# ui_front.net
KiCad netlist of a schematic drawn in Altium Designer
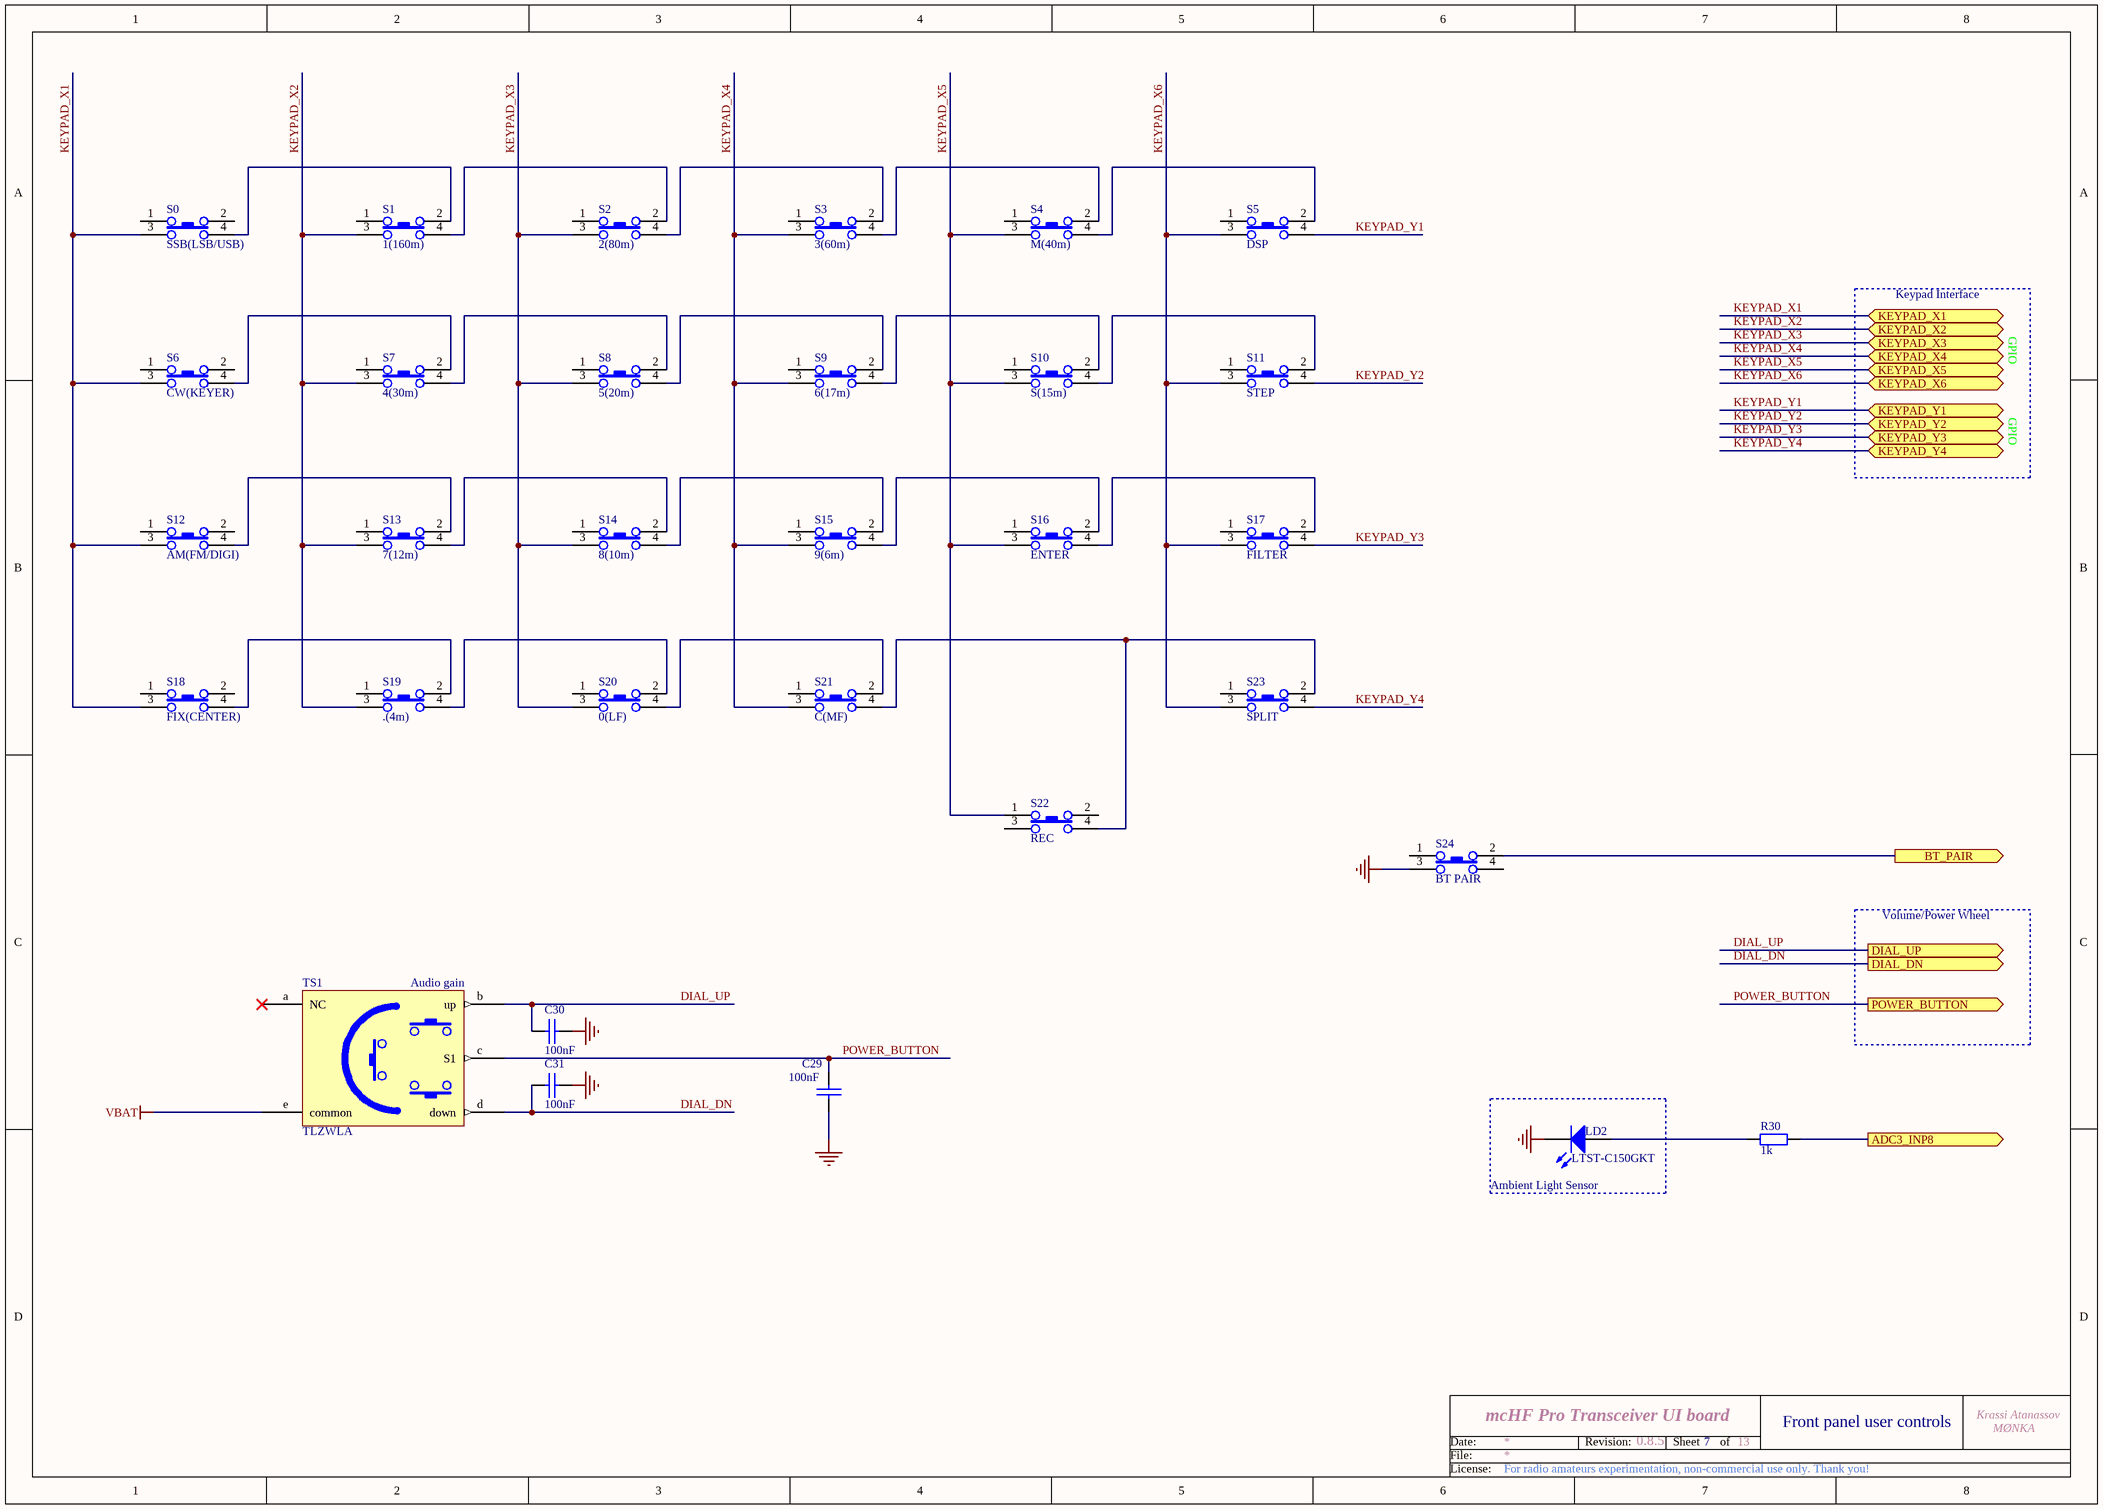
[diagram p0: ui_front.SchDoc]

(export (version "E")
  (design (tool "Eeschema 10.0.6"))
  (components
    (comp (ref "C29")
      (value "100nF")
      (footprint "0805")
      (description "Capacitor")
      (libsource (lib "mcHF_ui") (part "CAP"))
    )
    (comp (ref "C30")
      (value "100nF")
      (footprint "0805")
      (description "Capacitor")
      (libsource (lib "mcHF_ui") (part "CAP"))
    )
    (comp (ref "C31")
      (value "100nF")
      (footprint "0805")
      (description "Capacitor")
      (libsource (lib "mcHF_ui") (part "CAP"))
    )
    (comp (ref "LD2")
      (value "LTST-C150GKT")
      (footprint "1206_Elec_Cap")
      (description "LED 3mm")
      (libsource (lib "mcHF_ui") (part "LED2"))
    )
    (comp (ref "R30")
      (value "1k")
      (footprint "0805")
      (description "Resistor")
      (libsource (lib "mcHF_ui") (part "RES"))
    )
    (comp (ref "S0")
      (value "SSB(LSB/USB)")
      (footprint "BUTTON_SMD2")
      (description "Push Button")
      (libsource (lib "__ui") (part "SW-PB"))
    )
    (comp (ref "S1")
      (value "1(160m)")
      (footprint "BUTTON_SMD2")
      (description "Push Button")
      (libsource (lib "__ui") (part "SW-PB"))
    )
    (comp (ref "S2")
      (value "2(80m)")
      (footprint "BUTTON_SMD2")
      (description "Push Button")
      (libsource (lib "__ui") (part "SW-PB"))
    )
    (comp (ref "S3")
      (value "3(60m)")
      (footprint "BUTTON_SMD2")
      (description "Push Button")
      (libsource (lib "__ui") (part "SW-PB"))
    )
    (comp (ref "S4")
      (value "M(40m)")
      (footprint "BUTTON_SMD2")
      (description "Push Button")
      (libsource (lib "__ui") (part "SW-PB"))
    )
    (comp (ref "S5")
      (value "DSP")
      (footprint "BUTTON_SMD2")
      (description "Push Button")
      (libsource (lib "__ui") (part "SW-PB"))
    )
    (comp (ref "S6")
      (value "CW(KEYER)")
      (footprint "BUTTON_SMD2")
      (description "Push Button")
      (libsource (lib "__ui") (part "SW-PB"))
    )
    (comp (ref "S7")
      (value "4(30m)")
      (footprint "BUTTON_SMD2")
      (description "Push Button")
      (libsource (lib "__ui") (part "SW-PB"))
    )
    (comp (ref "S8")
      (value "5(20m)")
      (footprint "BUTTON_SMD2")
      (description "Push Button")
      (libsource (lib "__ui") (part "SW-PB"))
    )
    (comp (ref "S9")
      (value "6(17m)")
      (footprint "BUTTON_SMD2")
      (description "Push Button")
      (libsource (lib "__ui") (part "SW-PB"))
    )
    (comp (ref "S10")
      (value "S(15m)")
      (footprint "BUTTON_SMD2")
      (description "Push Button")
      (libsource (lib "__ui") (part "SW-PB"))
    )
    (comp (ref "S11")
      (value "STEP")
      (footprint "BUTTON_SMD2")
      (description "Push Button")
      (libsource (lib "__ui") (part "SW-PB"))
    )
    (comp (ref "S12")
      (value "AM(FM/DIGI)")
      (footprint "BUTTON_SMD2")
      (description "Push Button")
      (libsource (lib "__ui") (part "SW-PB"))
    )
    (comp (ref "S13")
      (value "7(12m)")
      (footprint "BUTTON_SMD2")
      (description "Push Button")
      (libsource (lib "__ui") (part "SW-PB"))
    )
    (comp (ref "S14")
      (value "8(10m)")
      (footprint "BUTTON_SMD2")
      (description "Push Button")
      (libsource (lib "__ui") (part "SW-PB"))
    )
    (comp (ref "S15")
      (value "9(6m)")
      (footprint "BUTTON_SMD2")
      (description "Push Button")
      (libsource (lib "__ui") (part "SW-PB"))
    )
    (comp (ref "S16")
      (value "ENTER")
      (footprint "BUTTON_SMD2")
      (description "Push Button")
      (libsource (lib "__ui") (part "SW-PB"))
    )
    (comp (ref "S17")
      (value "FILTER")
      (footprint "BUTTON_SMD2")
      (description "Push Button")
      (libsource (lib "__ui") (part "SW-PB"))
    )
    (comp (ref "S18")
      (value "FIX(CENTER)")
      (footprint "BUTTON_SMD2")
      (description "Push Button")
      (libsource (lib "__ui") (part "SW-PB"))
    )
    (comp (ref "S19")
      (value ".(4m)")
      (footprint "BUTTON_SMD2")
      (description "Push Button")
      (libsource (lib "__ui") (part "SW-PB"))
    )
    (comp (ref "S20")
      (value "0(LF)")
      (footprint "BUTTON_SMD2")
      (description "Push Button")
      (libsource (lib "__ui") (part "SW-PB"))
    )
    (comp (ref "S21")
      (value "C(MF)")
      (footprint "BUTTON_SMD2")
      (description "Push Button")
      (libsource (lib "__ui") (part "SW-PB"))
    )
    (comp (ref "S22")
      (value "REC")
      (footprint "BUTTON_SMD3")
      (description "Push Side Button")
      (libsource (lib "__ui") (part "SW-PBS"))
    )
    (comp (ref "S23")
      (value "SPLIT")
      (footprint "BUTTON_SMD2")
      (description "Push Button")
      (libsource (lib "__ui") (part "SW-PB"))
    )
    (comp (ref "S24")
      (value "BT PAIR")
      (footprint "BUTTON_SMD3")
      (description "Push Side Button")
      (libsource (lib "__ui") (part "SW-PBS"))
    )
    (comp (ref "TS1")
      (value "TLZWLA")
      (footprint "TLZWLA")
      (description "Thumbwheel Toggle Switch")
      (libsource (lib "__ui") (part "TLZWLA"))
    )
  )
  (nets
    (net (code "1") (name "/ADC3_INP8") (class "Default")
      (node (ref "R30") (pin "1") (pinfunction "1_1") (pintype "passive"))
    )
    (net (code "2") (name "/BT_PAIR") (class "Default")
      (node (ref "S24") (pin "2") (pinfunction "2_2") (pintype "passive"))
    )
    (net (code "3") (name "/DIAL_DN") (class "Default")
      (node (ref "C31") (pin "1") (pinfunction "1_1") (pintype "passive"))
      (node (ref "TS1") (pin "d") (pinfunction "down_d") (pintype "output"))
    )
    (net (code "4") (name "/DIAL_UP") (class "Default")
      (node (ref "C30") (pin "1") (pinfunction "1_1") (pintype "passive"))
      (node (ref "TS1") (pin "b") (pinfunction "up_b") (pintype "output"))
    )
    (net (code "5") (name "/KEYPAD_X1") (class "Default")
      (node (ref "S0") (pin "3") (pinfunction "3_3") (pintype "passive"))
      (node (ref "S12") (pin "3") (pinfunction "3_3") (pintype "passive"))
      (node (ref "S18") (pin "3") (pinfunction "3_3") (pintype "passive"))
      (node (ref "S6") (pin "3") (pinfunction "3_3") (pintype "passive"))
    )
    (net (code "6") (name "/KEYPAD_X2") (class "Default")
      (node (ref "S1") (pin "3") (pinfunction "3_3") (pintype "passive"))
      (node (ref "S13") (pin "3") (pinfunction "3_3") (pintype "passive"))
      (node (ref "S19") (pin "3") (pinfunction "3_3") (pintype "passive"))
      (node (ref "S7") (pin "3") (pinfunction "3_3") (pintype "passive"))
    )
    (net (code "7") (name "/KEYPAD_X3") (class "Default")
      (node (ref "S14") (pin "3") (pinfunction "3_3") (pintype "passive"))
      (node (ref "S2") (pin "3") (pinfunction "3_3") (pintype "passive"))
      (node (ref "S20") (pin "3") (pinfunction "3_3") (pintype "passive"))
      (node (ref "S8") (pin "3") (pinfunction "3_3") (pintype "passive"))
    )
    (net (code "8") (name "/KEYPAD_X4") (class "Default")
      (node (ref "S15") (pin "3") (pinfunction "3_3") (pintype "passive"))
      (node (ref "S21") (pin "3") (pinfunction "3_3") (pintype "passive"))
      (node (ref "S3") (pin "3") (pinfunction "3_3") (pintype "passive"))
      (node (ref "S9") (pin "3") (pinfunction "3_3") (pintype "passive"))
    )
    (net (code "9") (name "/KEYPAD_X5") (class "Default")
      (node (ref "S10") (pin "3") (pinfunction "3_3") (pintype "passive"))
      (node (ref "S16") (pin "3") (pinfunction "3_3") (pintype "passive"))
      (node (ref "S22") (pin "1") (pinfunction "1_1") (pintype "passive"))
      (node (ref "S4") (pin "3") (pinfunction "3_3") (pintype "passive"))
    )
    (net (code "10") (name "/KEYPAD_X6") (class "Default")
      (node (ref "S11") (pin "3") (pinfunction "3_3") (pintype "passive"))
      (node (ref "S17") (pin "3") (pinfunction "3_3") (pintype "passive"))
      (node (ref "S23") (pin "3") (pinfunction "3_3") (pintype "passive"))
      (node (ref "S5") (pin "3") (pinfunction "3_3") (pintype "passive"))
    )
    (net (code "11") (name "/KEYPAD_Y1") (class "Default")
      (node (ref "S5") (pin "4") (pinfunction "4_4") (pintype "passive"))
    )
    (net (code "12") (name "/KEYPAD_Y2") (class "Default")
      (node (ref "S11") (pin "4") (pinfunction "4_4") (pintype "passive"))
    )
    (net (code "13") (name "/KEYPAD_Y3") (class "Default")
      (node (ref "S17") (pin "4") (pinfunction "4_4") (pintype "passive"))
    )
    (net (code "14") (name "/KEYPAD_Y4") (class "Default")
      (node (ref "S23") (pin "4") (pinfunction "4_4") (pintype "passive"))
    )
    (net (code "15") (name "/POWER_BUTTON") (class "Default")
      (node (ref "C29") (pin "2") (pinfunction "2_2") (pintype "passive"))
      (node (ref "TS1") (pin "c") (pinfunction "S1_c") (pintype "output"))
    )
    (net (code "16") (name "GND") (class "Default")
      (node (ref "C29") (pin "1") (pinfunction "1_1") (pintype "passive"))
      (node (ref "C30") (pin "2") (pinfunction "2_2") (pintype "passive"))
      (node (ref "C31") (pin "2") (pinfunction "2_2") (pintype "passive"))
      (node (ref "LD2") (pin "2") (pinfunction "K_2") (pintype "passive"))
      (node (ref "S24") (pin "3") (pinfunction "3_3") (pintype "passive"))
    )
    (net (code "17") (name "Net-(LD2-A)") (class "Default")
      (node (ref "LD2") (pin "1") (pinfunction "A_1") (pintype "passive"))
      (node (ref "R30") (pin "2") (pinfunction "2_2") (pintype "passive"))
    )
    (net (code "18") (name "Net-(S0-Pad4)") (class "Default")
      (node (ref "S0") (pin "4") (pinfunction "4_4") (pintype "passive"))
      (node (ref "S1") (pin "2") (pinfunction "2_2") (pintype "passive"))
    )
    (net (code "19") (name "Net-(S1-Pad4)") (class "Default")
      (node (ref "S1") (pin "4") (pinfunction "4_4") (pintype "passive"))
      (node (ref "S2") (pin "2") (pinfunction "2_2") (pintype "passive"))
    )
    (net (code "20") (name "Net-(S2-Pad4)") (class "Default")
      (node (ref "S2") (pin "4") (pinfunction "4_4") (pintype "passive"))
      (node (ref "S3") (pin "2") (pinfunction "2_2") (pintype "passive"))
    )
    (net (code "21") (name "Net-(S3-Pad4)") (class "Default")
      (node (ref "S3") (pin "4") (pinfunction "4_4") (pintype "passive"))
      (node (ref "S4") (pin "2") (pinfunction "2_2") (pintype "passive"))
    )
    (net (code "22") (name "Net-(S4-Pad4)") (class "Default")
      (node (ref "S4") (pin "4") (pinfunction "4_4") (pintype "passive"))
      (node (ref "S5") (pin "2") (pinfunction "2_2") (pintype "passive"))
    )
    (net (code "23") (name "Net-(S6-Pad4)") (class "Default")
      (node (ref "S6") (pin "4") (pinfunction "4_4") (pintype "passive"))
      (node (ref "S7") (pin "2") (pinfunction "2_2") (pintype "passive"))
    )
    (net (code "24") (name "Net-(S7-Pad4)") (class "Default")
      (node (ref "S7") (pin "4") (pinfunction "4_4") (pintype "passive"))
      (node (ref "S8") (pin "2") (pinfunction "2_2") (pintype "passive"))
    )
    (net (code "25") (name "Net-(S8-Pad4)") (class "Default")
      (node (ref "S8") (pin "4") (pinfunction "4_4") (pintype "passive"))
      (node (ref "S9") (pin "2") (pinfunction "2_2") (pintype "passive"))
    )
    (net (code "26") (name "Net-(S10-Pad2)") (class "Default")
      (node (ref "S10") (pin "2") (pinfunction "2_2") (pintype "passive"))
      (node (ref "S9") (pin "4") (pinfunction "4_4") (pintype "passive"))
    )
    (net (code "27") (name "Net-(S10-Pad4)") (class "Default")
      (node (ref "S10") (pin "4") (pinfunction "4_4") (pintype "passive"))
      (node (ref "S11") (pin "2") (pinfunction "2_2") (pintype "passive"))
    )
    (net (code "28") (name "Net-(S12-Pad4)") (class "Default")
      (node (ref "S12") (pin "4") (pinfunction "4_4") (pintype "passive"))
      (node (ref "S13") (pin "2") (pinfunction "2_2") (pintype "passive"))
    )
    (net (code "29") (name "Net-(S13-Pad4)") (class "Default")
      (node (ref "S13") (pin "4") (pinfunction "4_4") (pintype "passive"))
      (node (ref "S14") (pin "2") (pinfunction "2_2") (pintype "passive"))
    )
    (net (code "30") (name "Net-(S14-Pad4)") (class "Default")
      (node (ref "S14") (pin "4") (pinfunction "4_4") (pintype "passive"))
      (node (ref "S15") (pin "2") (pinfunction "2_2") (pintype "passive"))
    )
    (net (code "31") (name "Net-(S15-Pad4)") (class "Default")
      (node (ref "S15") (pin "4") (pinfunction "4_4") (pintype "passive"))
      (node (ref "S16") (pin "2") (pinfunction "2_2") (pintype "passive"))
    )
    (net (code "32") (name "Net-(S16-Pad4)") (class "Default")
      (node (ref "S16") (pin "4") (pinfunction "4_4") (pintype "passive"))
      (node (ref "S17") (pin "2") (pinfunction "2_2") (pintype "passive"))
    )
    (net (code "33") (name "Net-(S18-Pad4)") (class "Default")
      (node (ref "S18") (pin "4") (pinfunction "4_4") (pintype "passive"))
      (node (ref "S19") (pin "2") (pinfunction "2_2") (pintype "passive"))
    )
    (net (code "34") (name "Net-(S19-Pad4)") (class "Default")
      (node (ref "S19") (pin "4") (pinfunction "4_4") (pintype "passive"))
      (node (ref "S20") (pin "2") (pinfunction "2_2") (pintype "passive"))
    )
    (net (code "35") (name "Net-(S20-Pad4)") (class "Default")
      (node (ref "S20") (pin "4") (pinfunction "4_4") (pintype "passive"))
      (node (ref "S21") (pin "2") (pinfunction "2_2") (pintype "passive"))
    )
    (net (code "36") (name "Net-(S21-Pad4)") (class "Default")
      (node (ref "S21") (pin "4") (pinfunction "4_4") (pintype "passive"))
      (node (ref "S22") (pin "4") (pinfunction "4_4") (pintype "passive"))
      (node (ref "S23") (pin "2") (pinfunction "2_2") (pintype "passive"))
    )
    (net (code "37") (name "VBAT") (class "Default")
      (node (ref "TS1") (pin "e") (pinfunction "common_e") (pintype "passive"))
    )
    (net (code "38") (name "unconnected-(S0-Pad1)") (class "Default")
      (node (ref "S0") (pin "1") (pinfunction "1_1") (pintype "passive"))
    )
    (net (code "39") (name "unconnected-(S0-Pad2)") (class "Default")
      (node (ref "S0") (pin "2") (pinfunction "2_2") (pintype "passive"))
    )
    (net (code "40") (name "unconnected-(S1-Pad1)") (class "Default")
      (node (ref "S1") (pin "1") (pinfunction "1_1") (pintype "passive"))
    )
    (net (code "41") (name "unconnected-(S2-Pad1)") (class "Default")
      (node (ref "S2") (pin "1") (pinfunction "1_1") (pintype "passive"))
    )
    (net (code "42") (name "unconnected-(S3-Pad1)") (class "Default")
      (node (ref "S3") (pin "1") (pinfunction "1_1") (pintype "passive"))
    )
    (net (code "43") (name "unconnected-(S4-Pad1)") (class "Default")
      (node (ref "S4") (pin "1") (pinfunction "1_1") (pintype "passive"))
    )
    (net (code "44") (name "unconnected-(S5-Pad1)") (class "Default")
      (node (ref "S5") (pin "1") (pinfunction "1_1") (pintype "passive"))
    )
    (net (code "45") (name "unconnected-(S6-Pad1)") (class "Default")
      (node (ref "S6") (pin "1") (pinfunction "1_1") (pintype "passive"))
    )
    (net (code "46") (name "unconnected-(S6-Pad2)") (class "Default")
      (node (ref "S6") (pin "2") (pinfunction "2_2") (pintype "passive"))
    )
    (net (code "47") (name "unconnected-(S7-Pad1)") (class "Default")
      (node (ref "S7") (pin "1") (pinfunction "1_1") (pintype "passive"))
    )
    (net (code "48") (name "unconnected-(S8-Pad1)") (class "Default")
      (node (ref "S8") (pin "1") (pinfunction "1_1") (pintype "passive"))
    )
    (net (code "49") (name "unconnected-(S9-Pad1)") (class "Default")
      (node (ref "S9") (pin "1") (pinfunction "1_1") (pintype "passive"))
    )
    (net (code "50") (name "unconnected-(S10-Pad1)") (class "Default")
      (node (ref "S10") (pin "1") (pinfunction "1_1") (pintype "passive"))
    )
    (net (code "51") (name "unconnected-(S11-Pad1)") (class "Default")
      (node (ref "S11") (pin "1") (pinfunction "1_1") (pintype "passive"))
    )
    (net (code "52") (name "unconnected-(S12-Pad1)") (class "Default")
      (node (ref "S12") (pin "1") (pinfunction "1_1") (pintype "passive"))
    )
    (net (code "53") (name "unconnected-(S12-Pad2)") (class "Default")
      (node (ref "S12") (pin "2") (pinfunction "2_2") (pintype "passive"))
    )
    (net (code "54") (name "unconnected-(S13-Pad1)") (class "Default")
      (node (ref "S13") (pin "1") (pinfunction "1_1") (pintype "passive"))
    )
    (net (code "55") (name "unconnected-(S14-Pad1)") (class "Default")
      (node (ref "S14") (pin "1") (pinfunction "1_1") (pintype "passive"))
    )
    (net (code "56") (name "unconnected-(S15-Pad1)") (class "Default")
      (node (ref "S15") (pin "1") (pinfunction "1_1") (pintype "passive"))
    )
    (net (code "57") (name "unconnected-(S16-Pad1)") (class "Default")
      (node (ref "S16") (pin "1") (pinfunction "1_1") (pintype "passive"))
    )
    (net (code "58") (name "unconnected-(S17-Pad1)") (class "Default")
      (node (ref "S17") (pin "1") (pinfunction "1_1") (pintype "passive"))
    )
    (net (code "59") (name "unconnected-(S18-Pad1)") (class "Default")
      (node (ref "S18") (pin "1") (pinfunction "1_1") (pintype "passive"))
    )
    (net (code "60") (name "unconnected-(S18-Pad2)") (class "Default")
      (node (ref "S18") (pin "2") (pinfunction "2_2") (pintype "passive"))
    )
    (net (code "61") (name "unconnected-(S19-Pad1)") (class "Default")
      (node (ref "S19") (pin "1") (pinfunction "1_1") (pintype "passive"))
    )
    (net (code "62") (name "unconnected-(S20-Pad1)") (class "Default")
      (node (ref "S20") (pin "1") (pinfunction "1_1") (pintype "passive"))
    )
    (net (code "63") (name "unconnected-(S21-Pad1)") (class "Default")
      (node (ref "S21") (pin "1") (pinfunction "1_1") (pintype "passive"))
    )
    (net (code "64") (name "unconnected-(S22-Pad2)") (class "Default")
      (node (ref "S22") (pin "2") (pinfunction "2_2") (pintype "passive"))
    )
    (net (code "65") (name "unconnected-(S22-Pad3)") (class "Default")
      (node (ref "S22") (pin "3") (pinfunction "3_3") (pintype "passive"))
    )
    (net (code "66") (name "unconnected-(S23-Pad1)") (class "Default")
      (node (ref "S23") (pin "1") (pinfunction "1_1") (pintype "passive"))
    )
    (net (code "67") (name "unconnected-(S24-Pad1)") (class "Default")
      (node (ref "S24") (pin "1") (pinfunction "1_1") (pintype "passive"))
    )
    (net (code "68") (name "unconnected-(S24-Pad4)") (class "Default")
      (node (ref "S24") (pin "4") (pinfunction "4_4") (pintype "passive"))
    )
    (net (code "69") (name "unconnected-(TS1-NC-Pada)") (class "Default")
      (node (ref "TS1") (pin "a") (pinfunction "NC_a") (pintype "passive+no_connect"))
    )
  )
)
